# IMU.net
KiCad netlist of a schematic drawn in Altium Designer
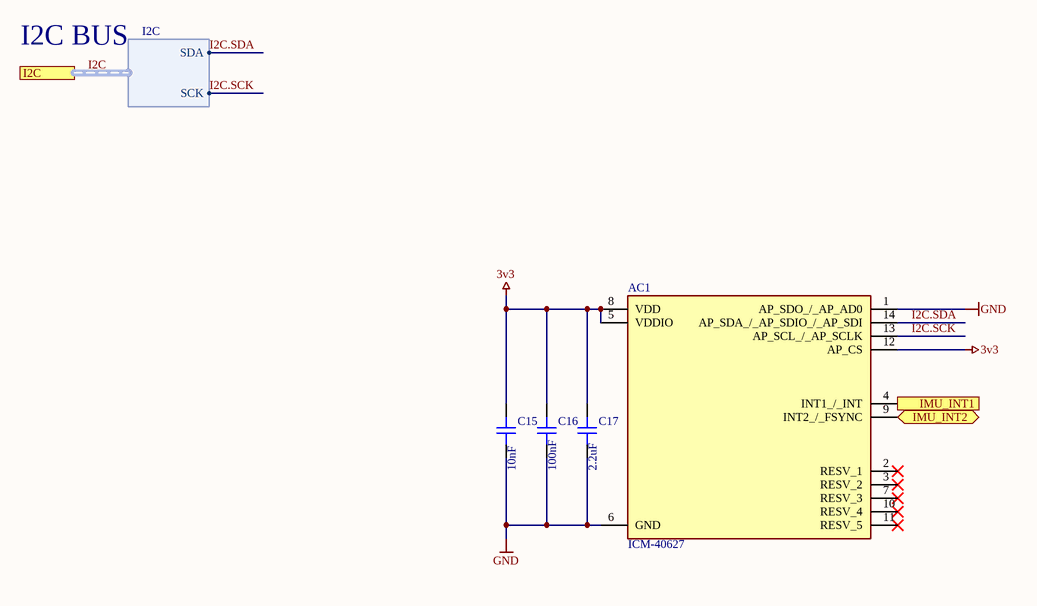
[diagram p0: IMU.SchDoc]

(export (version "E")
  (design (tool "Eeschema 10.0.6"))
  (components
    (comp (ref "AC1")
      (value "ICM-40627")
      (footprint "Footprint-Lib-PhilsLab:ICM-40627")
      (description "Accelerometer")
      (fields (field (name "MOUSER PART NUMBER") "410-ICM-40627"))
      (libsource (lib "Schematic-Lib-PhilsLab") (part "ICM-40627"))
    )
    (comp (ref "C15")
      (value "10nF")
      (footprint "CAP_0402")
      (description "Capacitor SMD 0402 10V")
      (fields (field (name "Comment") "C0402_10V"))
      (libsource (lib "Schematic-Lib-PhilsLab") (part "CAP_0402_10V"))
    )
    (comp (ref "C16")
      (value "100nF")
      (footprint "CAP_0402")
      (description "Capacitor SMD 0402 10V")
      (fields (field (name "Comment") "C0402_10V"))
      (libsource (lib "Schematic-Lib-PhilsLab") (part "CAP_0402_10V"))
    )
    (comp (ref "C17")
      (value "2.2uF")
      (footprint "CAP_0402")
      (description "Capacitor SMD 0402 10V")
      (fields (field (name "Comment") "C0402_10V"))
      (libsource (lib "Schematic-Lib-PhilsLab") (part "CAP_0402_10V"))
    )
  )
  (nets
    (net (code "2") (name "/I2C.SCK") (class "Default")
      (node (ref "AC1") (pin "13") (pinfunction "AP_SCL_/_AP_SCLK_13") (pintype "passive"))
    )
    (net (code "3") (name "/I2C.SDA") (class "Default")
      (node (ref "AC1") (pin "14") (pinfunction "AP_SDA_/_AP_SDIO_/_AP_SDI_14") (pintype "passive"))
    )
    (net (code "5") (name "/IMU_INT1") (class "Default")
      (node (ref "AC1") (pin "4") (pinfunction "INT1_/_INT_4") (pintype "passive"))
    )
    (net (code "6") (name "/IMU_INT2") (class "Default")
      (node (ref "AC1") (pin "9") (pinfunction "INT2_/_FSYNC_9") (pintype "passive"))
    )
    (net (code "7") (name "3v3") (class "Default")
      (node (ref "AC1") (pin "12") (pinfunction "AP_CS_12") (pintype "passive"))
      (node (ref "AC1") (pin "5") (pinfunction "VDDIO_5") (pintype "passive"))
      (node (ref "AC1") (pin "8") (pinfunction "VDD_8") (pintype "passive"))
      (node (ref "C15") (pin "2") (pinfunction "2_2") (pintype "passive"))
      (node (ref "C16") (pin "2") (pinfunction "2_2") (pintype "passive"))
      (node (ref "C17") (pin "2") (pinfunction "2_2") (pintype "passive"))
    )
    (net (code "8") (name "GND") (class "Default")
      (node (ref "AC1") (pin "1") (pinfunction "AP_SDO_/_AP_AD0_1") (pintype "passive"))
      (node (ref "AC1") (pin "6") (pinfunction "GND_6") (pintype "passive"))
      (node (ref "C15") (pin "1") (pinfunction "1_1") (pintype "passive"))
      (node (ref "C16") (pin "1") (pinfunction "1_1") (pintype "passive"))
      (node (ref "C17") (pin "1") (pinfunction "1_1") (pintype "passive"))
    )
    (net (code "9") (name "unconnected-(AC1-RESV_1-Pad2)") (class "Default")
      (node (ref "AC1") (pin "2") (pinfunction "RESV_1_2") (pintype "passive+no_connect"))
    )
    (net (code "10") (name "unconnected-(AC1-RESV_2-Pad3)") (class "Default")
      (node (ref "AC1") (pin "3") (pinfunction "RESV_2_3") (pintype "passive+no_connect"))
    )
    (net (code "11") (name "unconnected-(AC1-RESV_3-Pad7)") (class "Default")
      (node (ref "AC1") (pin "7") (pinfunction "RESV_3_7") (pintype "passive+no_connect"))
    )
    (net (code "12") (name "unconnected-(AC1-RESV_4-Pad10)") (class "Default")
      (node (ref "AC1") (pin "10") (pinfunction "RESV_4_10") (pintype "passive+no_connect"))
    )
    (net (code "13") (name "unconnected-(AC1-RESV_5-Pad11)") (class "Default")
      (node (ref "AC1") (pin "11") (pinfunction "RESV_5_11") (pintype "passive+no_connect"))
    )
  )
)
